# esquematico.net
KiCad netlist of a schematic drawn in EAGLE
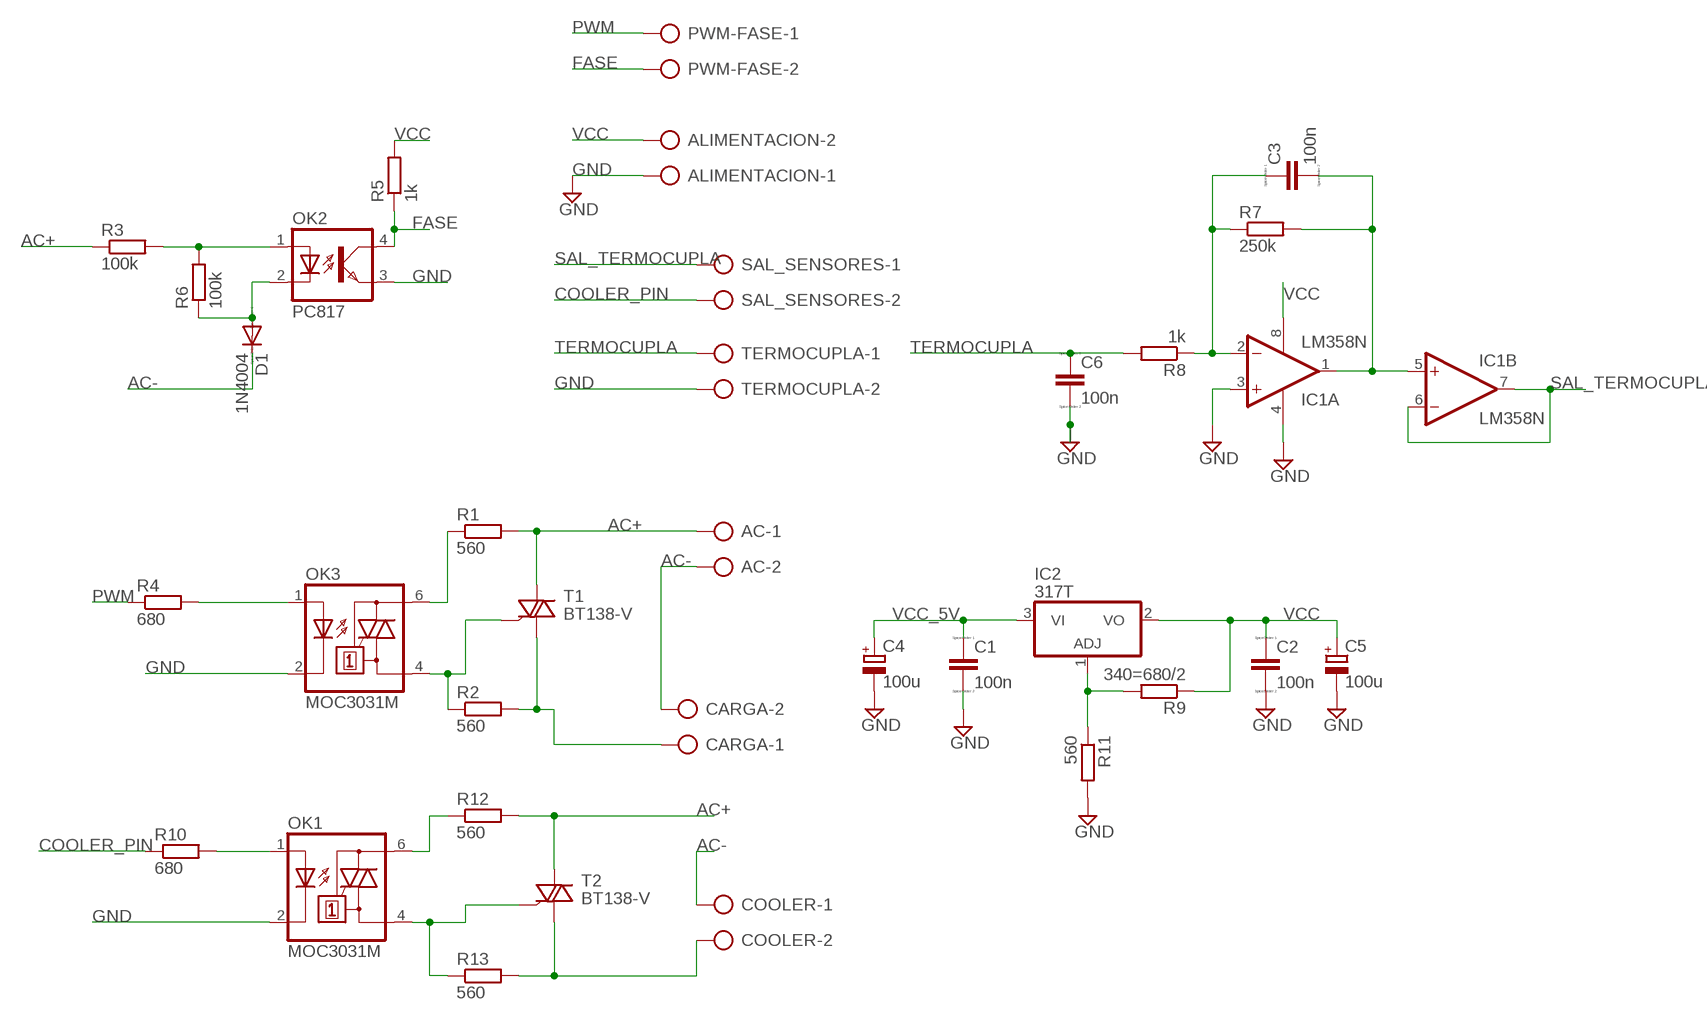
[diagram p0: schematic, sheet 1]

(export (version "E")
  (design (tool "Eeschema 10.0.6"))
  (components
    (comp (ref "AC")
      (value "AK300/2")
      (footprint "eagle-import:AK300_2")
      (libsource (lib "eagle-import") (part "AK300/2"))
    )
    (comp (ref "ALIMENTACION")
      (value "AK300/2")
      (footprint "eagle-import:AK300_2")
      (libsource (lib "eagle-import") (part "AK300/2"))
    )
    (comp (ref "C1")
      (value "100n")
      (footprint "eagle-import:C1206")
      (libsource (lib "eagle-import") (part "CC1206"))
    )
    (comp (ref "C2")
      (value "100n")
      (footprint "eagle-import:C1206")
      (libsource (lib "eagle-import") (part "CC1206"))
    )
    (comp (ref "C3")
      (value "100n")
      (footprint "eagle-import:C1206")
      (libsource (lib "eagle-import") (part "CC1206"))
    )
    (comp (ref "C4")
      (value "100u")
      (footprint "eagle-import:E1,8-4")
      (libsource (lib "eagle-import") (part "CPOL-EUE1.8-4"))
    )
    (comp (ref "C5")
      (value "100u")
      (footprint "eagle-import:E1,8-4")
      (libsource (lib "eagle-import") (part "CPOL-EUE1.8-4"))
    )
    (comp (ref "C6")
      (value "100n")
      (footprint "eagle-import:C1206")
      (libsource (lib "eagle-import") (part "CC1206"))
    )
    (comp (ref "CARGA")
      (value "AK300/2")
      (footprint "eagle-import:AK300_2")
      (libsource (lib "eagle-import") (part "AK300/2"))
    )
    (comp (ref "COOLER")
      (value "AK300/2")
      (footprint "eagle-import:AK300_2")
      (libsource (lib "eagle-import") (part "AK300/2"))
    )
    (comp (ref "D1")
      (value "1N4004")
      (footprint "eagle-import:DO41-10")
      (libsource (lib "eagle-import") (part "1N4004"))
    )
    (comp (ref "IC1")
      (value "LM358N")
      (footprint "eagle-import:DIL08")
      (libsource (lib "eagle-import") (part "LM358N"))
    )
    (comp (ref "IC2")
      (value "317T")
      (footprint "eagle-import:TO220H")
      (libsource (lib "eagle-import") (part "317T"))
    )
    (comp (ref "OK1")
      (value "MOC3031M")
      (footprint "eagle-import:DIL06")
      (fields (field (name "MF") "FAIRCHILD SEMICONDUCTOR"))
      (libsource (lib "eagle-import") (part "MOC3031M"))
    )
    (comp (ref "OK2")
      (value "PC817")
      (footprint "eagle-import:DIL04")
      (fields (field (name "MPN") "PC817X4J000F"))
      (libsource (lib "eagle-import") (part "PC817"))
    )
    (comp (ref "OK3")
      (value "MOC3031M")
      (footprint "eagle-import:DIL06")
      (fields (field (name "MF") "FAIRCHILD SEMICONDUCTOR"))
      (libsource (lib "eagle-import") (part "MOC3031M"))
    )
    (comp (ref "PWM-FASE")
      (value "AK300/2")
      (footprint "eagle-import:AK300_2")
      (libsource (lib "eagle-import") (part "AK300/2"))
    )
    (comp (ref "R1")
      (value "560")
      (footprint "eagle-import:R1206")
      (libsource (lib "eagle-import") (part "R-EU_R1206"))
    )
    (comp (ref "R2")
      (value "560")
      (footprint "eagle-import:R1206")
      (libsource (lib "eagle-import") (part "R-EU_R1206"))
    )
    (comp (ref "R3")
      (value "100k")
      (footprint "eagle-import:0207_10")
      (libsource (lib "eagle-import") (part "R-EU_0207/10"))
    )
    (comp (ref "R4")
      (value "680")
      (footprint "eagle-import:R1206")
      (libsource (lib "eagle-import") (part "R-EU_R1206"))
    )
    (comp (ref "R5")
      (value "1k")
      (footprint "eagle-import:R1206")
      (libsource (lib "eagle-import") (part "R-EU_R1206"))
    )
    (comp (ref "R6")
      (value "100k")
      (footprint "eagle-import:R1206")
      (libsource (lib "eagle-import") (part "R-EU_R1206"))
    )
    (comp (ref "R7")
      (value "250k")
      (footprint "eagle-import:R1206")
      (libsource (lib "eagle-import") (part "R-EU_R1206"))
    )
    (comp (ref "R8")
      (value "1k")
      (footprint "eagle-import:R1206")
      (libsource (lib "eagle-import") (part "R-EU_R1206"))
    )
    (comp (ref "R9")
      (value "340=680/2")
      (footprint "eagle-import:R1206")
      (libsource (lib "eagle-import") (part "R-EU_R1206"))
    )
    (comp (ref "R10")
      (value "680")
      (footprint "eagle-import:R1206")
      (libsource (lib "eagle-import") (part "R-EU_R1206"))
    )
    (comp (ref "R11")
      (value "560")
      (footprint "eagle-import:R1206")
      (libsource (lib "eagle-import") (part "R-EU_R1206"))
    )
    (comp (ref "R12")
      (value "560")
      (footprint "eagle-import:R1206")
      (libsource (lib "eagle-import") (part "R-EU_R1206"))
    )
    (comp (ref "R13")
      (value "560")
      (footprint "eagle-import:R1206")
      (libsource (lib "eagle-import") (part "R-EU_R1206"))
    )
    (comp (ref "SAL_SENSORES")
      (value "AK300/2")
      (footprint "eagle-import:AK300_2")
      (libsource (lib "eagle-import") (part "AK300/2"))
    )
    (comp (ref "T1")
      (value "BT138-V")
      (footprint "eagle-import:TO220BV")
      (libsource (lib "eagle-import") (part "BT138-V"))
    )
    (comp (ref "T2")
      (value "BT138-V")
      (footprint "eagle-import:TO220BV")
      (libsource (lib "eagle-import") (part "BT138-V"))
    )
    (comp (ref "TERMOCUPLA")
      (value "AK300/2")
      (footprint "eagle-import:AK300_2")
      (libsource (lib "eagle-import") (part "AK300/2"))
    )
  )
  (nets
    (net (code "1") (name "/AC+") (class "Default")
      (node (ref "AC") (pin "1") (pinfunction "KL_1") (pintype "passive"))
      (node (ref "R1") (pin "2") (pinfunction "2_2") (pintype "passive"))
      (node (ref "R12") (pin "2") (pinfunction "2_2") (pintype "passive"))
      (node (ref "R3") (pin "1") (pinfunction "1_1") (pintype "passive"))
      (node (ref "T1") (pin "T2") (pinfunction "A2_T2") (pintype "passive"))
      (node (ref "T2") (pin "T2") (pinfunction "A2_T2") (pintype "passive"))
    )
    (net (code "2") (name "/AC-") (class "Default")
      (node (ref "AC") (pin "2") (pinfunction "KL_2") (pintype "passive"))
      (node (ref "CARGA") (pin "2") (pinfunction "KL_2") (pintype "passive"))
      (node (ref "COOLER") (pin "1") (pinfunction "KL_1") (pintype "passive"))
      (node (ref "D1") (pin "C") (pinfunction "C_C") (pintype "passive"))
    )
    (net (code "3") (name "/COOLER_PIN") (class "Default")
      (node (ref "R10") (pin "1") (pinfunction "1_1") (pintype "passive"))
      (node (ref "SAL_SENSORES") (pin "2") (pinfunction "KL_2") (pintype "passive"))
    )
    (net (code "4") (name "/FASE") (class "Default")
      (node (ref "OK2") (pin "4") (pinfunction "COL_4") (pintype "passive"))
      (node (ref "PWM-FASE") (pin "2") (pinfunction "KL_2") (pintype "passive"))
      (node (ref "R5") (pin "1") (pinfunction "1_1") (pintype "passive"))
    )
    (net (code "5") (name "/PWM") (class "Default")
      (node (ref "PWM-FASE") (pin "1") (pinfunction "KL_1") (pintype "passive"))
      (node (ref "R4") (pin "1") (pinfunction "1_1") (pintype "passive"))
    )
    (net (code "6") (name "/SAL_TERMOCUPLA") (class "Default")
      (node (ref "IC1") (pin "6") (pinfunction "-IN_6") (pintype "input"))
      (node (ref "IC1") (pin "7") (pinfunction "OUT_7") (pintype "output"))
      (node (ref "SAL_SENSORES") (pin "1") (pinfunction "KL_1") (pintype "passive"))
    )
    (net (code "7") (name "/TERMOCUPLA") (class "Default")
      (node (ref "C6") (pin "1") (pinfunction "1_1") (pintype "passive"))
      (node (ref "R8") (pin "2") (pinfunction "2_2") (pintype "passive"))
      (node (ref "TERMOCUPLA") (pin "1") (pinfunction "KL_1") (pintype "passive"))
    )
    (net (code "8") (name "/VCC") (class "Default")
      (node (ref "ALIMENTACION") (pin "2") (pinfunction "KL_2") (pintype "passive"))
      (node (ref "C2") (pin "1") (pinfunction "1_1") (pintype "passive"))
      (node (ref "C5") (pin "+") (pinfunction "+_+") (pintype "passive"))
      (node (ref "IC1") (pin "8") (pinfunction "V+_8") (pintype "power_in"))
      (node (ref "IC2") (pin "2") (pinfunction "VO_2") (pintype "passive"))
      (node (ref "R5") (pin "2") (pinfunction "2_2") (pintype "passive"))
      (node (ref "R9") (pin "1") (pinfunction "1_1") (pintype "passive"))
    )
    (net (code "9") (name "/VCC_5V") (class "Default")
      (node (ref "C1") (pin "1") (pinfunction "1_1") (pintype "passive"))
      (node (ref "C4") (pin "+") (pinfunction "+_+") (pintype "passive"))
      (node (ref "IC2") (pin "3") (pinfunction "VI_3") (pintype "input"))
    )
    (net (code "10") (name "GND") (class "Default")
      (node (ref "ALIMENTACION") (pin "1") (pinfunction "KL_1") (pintype "passive"))
      (node (ref "C1") (pin "2") (pinfunction "2_2") (pintype "passive"))
      (node (ref "C2") (pin "2") (pinfunction "2_2") (pintype "passive"))
      (node (ref "C4") (pin "-") (pinfunction "-_-") (pintype "passive"))
      (node (ref "C5") (pin "-") (pinfunction "-_-") (pintype "passive"))
      (node (ref "C6") (pin "2") (pinfunction "2_2") (pintype "passive"))
      (node (ref "IC1") (pin "3") (pinfunction "+IN_3") (pintype "input"))
      (node (ref "IC1") (pin "4") (pinfunction "V-_4") (pintype "power_in"))
      (node (ref "OK1") (pin "2") (pinfunction "C_2") (pintype "passive"))
      (node (ref "OK2") (pin "3") (pinfunction "EMIT_3") (pintype "passive"))
      (node (ref "OK3") (pin "2") (pinfunction "C_2") (pintype "passive"))
      (node (ref "R11") (pin "2") (pinfunction "2_2") (pintype "passive"))
      (node (ref "TERMOCUPLA") (pin "2") (pinfunction "KL_2") (pintype "passive"))
    )
    (net (code "11") (name "Net-(CARGAA-KL)") (class "Default")
      (node (ref "CARGA") (pin "1") (pinfunction "KL_1") (pintype "passive"))
      (node (ref "R2") (pin "2") (pinfunction "2_2") (pintype "passive"))
      (node (ref "T1") (pin "T1") (pinfunction "A1_T1") (pintype "passive"))
    )
    (net (code "12") (name "Net-(COOLERB-KL)") (class "Default")
      (node (ref "COOLER") (pin "2") (pinfunction "KL_2") (pintype "passive"))
      (node (ref "R13") (pin "2") (pinfunction "2_2") (pintype "passive"))
      (node (ref "T2") (pin "T1") (pinfunction "A1_T1") (pintype "passive"))
    )
    (net (code "13") (name "Net-(IC1A--IN)") (class "Default")
      (node (ref "C3") (pin "1") (pinfunction "1_1") (pintype "passive"))
      (node (ref "IC1") (pin "2") (pinfunction "-IN_2") (pintype "input"))
      (node (ref "R7") (pin "1") (pinfunction "1_1") (pintype "passive"))
      (node (ref "R8") (pin "1") (pinfunction "1_1") (pintype "passive"))
    )
    (net (code "14") (name "Net-(IC1A-OUT)") (class "Default")
      (node (ref "C3") (pin "2") (pinfunction "2_2") (pintype "passive"))
      (node (ref "IC1") (pin "1") (pinfunction "OUT_1") (pintype "output"))
      (node (ref "IC1") (pin "5") (pinfunction "+IN_5") (pintype "input"))
      (node (ref "R7") (pin "2") (pinfunction "2_2") (pintype "passive"))
    )
    (net (code "15") (name "Net-(IC2-ADJ)") (class "Default")
      (node (ref "IC2") (pin "1") (pinfunction "ADJ_1") (pintype "input"))
      (node (ref "R11") (pin "1") (pinfunction "1_1") (pintype "passive"))
      (node (ref "R9") (pin "2") (pinfunction "2_2") (pintype "passive"))
    )
    (net (code "16") (name "Net-(OK1-A)") (class "Default")
      (node (ref "OK1") (pin "1") (pinfunction "A_1") (pintype "passive"))
      (node (ref "R10") (pin "2") (pinfunction "2_2") (pintype "passive"))
    )
    (net (code "17") (name "Net-(OK1-A1)") (class "Default")
      (node (ref "OK1") (pin "4") (pinfunction "A1_4") (pintype "passive"))
      (node (ref "R13") (pin "1") (pinfunction "1_1") (pintype "passive"))
      (node (ref "T2") (pin "G") (pinfunction "G_G") (pintype "passive"))
    )
    (net (code "18") (name "Net-(OK1-A2)") (class "Default")
      (node (ref "OK1") (pin "6") (pinfunction "A2_6") (pintype "passive"))
      (node (ref "R12") (pin "1") (pinfunction "1_1") (pintype "passive"))
    )
    (net (code "19") (name "Net-(OK2-A)") (class "Default")
      (node (ref "OK2") (pin "1") (pinfunction "A_1") (pintype "passive"))
      (node (ref "R3") (pin "2") (pinfunction "2_2") (pintype "passive"))
      (node (ref "R6") (pin "2") (pinfunction "2_2") (pintype "passive"))
    )
    (net (code "20") (name "Net-(OK2-C)") (class "Default")
      (node (ref "D1") (pin "A") (pinfunction "A_A") (pintype "passive"))
      (node (ref "OK2") (pin "2") (pinfunction "C_2") (pintype "passive"))
      (node (ref "R6") (pin "1") (pinfunction "1_1") (pintype "passive"))
    )
    (net (code "21") (name "Net-(OK3-A)") (class "Default")
      (node (ref "OK3") (pin "1") (pinfunction "A_1") (pintype "passive"))
      (node (ref "R4") (pin "2") (pinfunction "2_2") (pintype "passive"))
    )
    (net (code "22") (name "Net-(OK3-A1)") (class "Default")
      (node (ref "OK3") (pin "4") (pinfunction "A1_4") (pintype "passive"))
      (node (ref "R2") (pin "1") (pinfunction "1_1") (pintype "passive"))
      (node (ref "T1") (pin "G") (pinfunction "G_G") (pintype "passive"))
    )
    (net (code "23") (name "Net-(OK3-A2)") (class "Default")
      (node (ref "OK3") (pin "6") (pinfunction "A2_6") (pintype "passive"))
      (node (ref "R1") (pin "1") (pinfunction "1_1") (pintype "passive"))
    )
  )
)
